# Power.net
KiCad netlist of a schematic drawn in Altium Designer
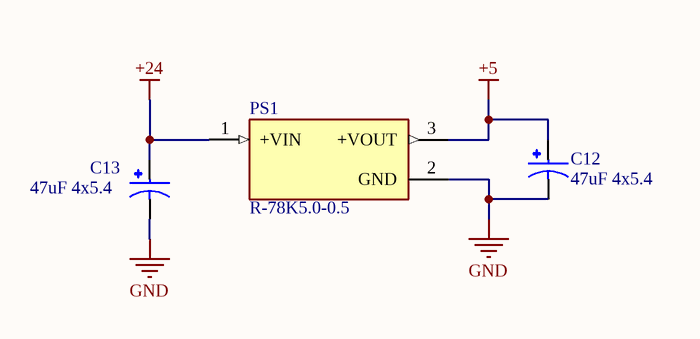
[diagram p0: Power.SchDoc]

(export (version "E")
  (design (tool "Eeschema 10.0.6"))
  (components
    (comp (ref "C12")
      (value "47uF 4x5.4")
      (footprint "Capacitors SMD:Electrolytic 4x5.4")
      (fields (field (name "MF") "Panasonic") (field (name "MP") "EEE-HA1E100WR"))
      (libsource (lib "Capacitors SMD") (part "Electrolytic 4x5.4"))
    )
    (comp (ref "C13")
      (value "47uF 4x5.4")
      (footprint "Capacitors SMD:Electrolytic 4x5.4")
      (fields (field (name "MF") "Panasonic") (field (name "MP") "EEE-HA1E100WR"))
      (libsource (lib "Capacitors SMD") (part "Electrolytic 4x5.4"))
    )
    (comp (ref "PS1")
      (value "R-78K5.0-0.5")
      (footprint "CONV_R-78K5.0-0.5")
      (description "0.5A DC/DC-Converter 'INNOLINE' SIP3 reg")
      (fields (field (name "MF") "Recom Power"))
      (libsource (lib "Voltage Regulators Through Hole") (part "R-78K5.0-0.5"))
    )
  )
  (nets
    (net (code "1") (name "+5") (class "Default")
      (node (ref "C12") (pin "1") (pinfunction "1_1") (pintype "passive"))
      (node (ref "PS1") (pin "3") (pinfunction "+VOUT_3") (pintype "output"))
    )
    (net (code "2") (name "+24") (class "Default")
      (node (ref "C13") (pin "1") (pinfunction "1_1") (pintype "passive"))
      (node (ref "PS1") (pin "1") (pinfunction "+VIN_1") (pintype "input"))
    )
    (net (code "3") (name "GND") (class "Default")
      (node (ref "C12") (pin "2") (pinfunction "2_2") (pintype "passive"))
      (node (ref "C13") (pin "2") (pinfunction "2_2") (pintype "passive"))
      (node (ref "PS1") (pin "2") (pinfunction "GND_2") (pintype "power_in"))
    )
  )
)
